# Logic_138.net
KiCad netlist of a schematic drawn in Altium Designer
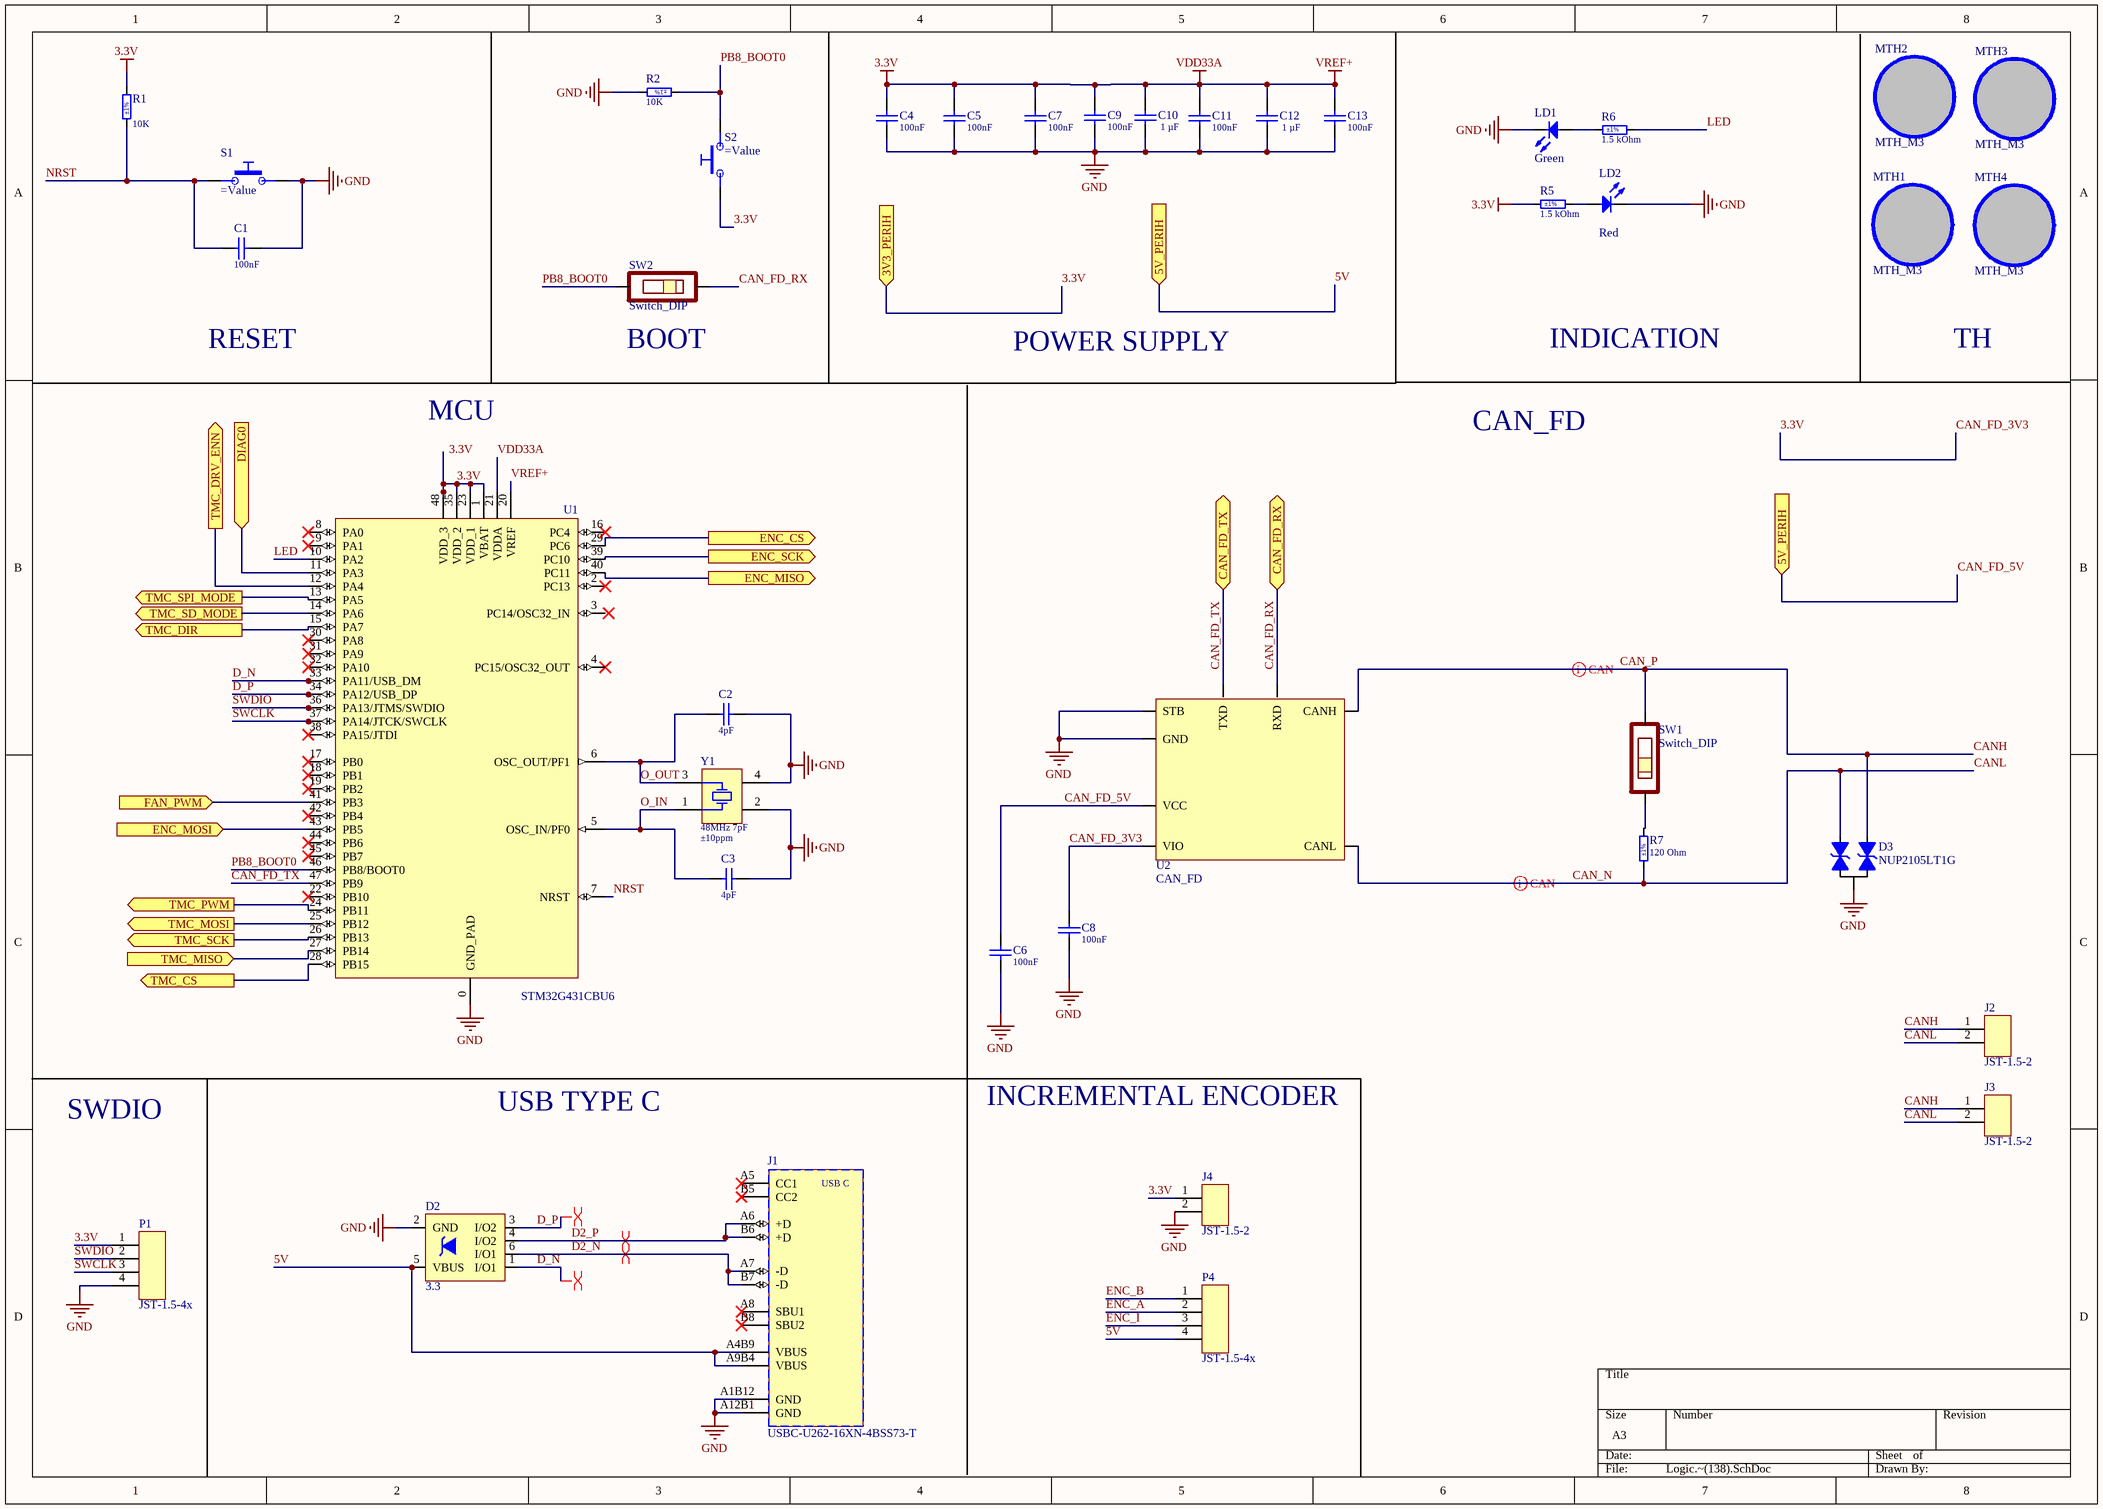
[diagram p0: Logic.~(138).SchDoc]

(export (version "E")
  (design (tool "Eeschema 10.0.6"))
  (components
    (comp (ref "C1")
      (value "100nF 16V X7R ±10%")
      (footprint "capasitors:0402")
      (description "Ceramic capacitor")
      (fields
        (field (name "VOLTAGE") "16V")
        (field (name "TOLERANCE") "±10%")
        (field (name "CAPACITANCE") "100nF")
      )
      (libsource (lib "passive") (part "Capacitor ceramic"))
    )
    (comp (ref "C2")
      (value "4pF 50V C0G (NP0) ±0.25 pF")
      (footprint "0402")
      (description "Ceramic capacitor")
      (fields
        (field (name "VOLTAGE") "50V")
        (field (name "TOLERANCE") "±0.25 pF")
        (field (name "CAPACITANCE") "4pF")
      )
      (libsource (lib "Integrated_Library_Rassipuha_ZEN") (part "Capacitor ceramic"))
    )
    (comp (ref "C3")
      (value "4pF 50V C0G (NP0) ±0.25 pF")
      (footprint "0402")
      (description "Ceramic capacitor")
      (fields
        (field (name "VOLTAGE") "50V")
        (field (name "TOLERANCE") "±0.25 pF")
        (field (name "CAPACITANCE") "4pF")
      )
      (libsource (lib "Integrated_Library_Rassipuha_ZEN") (part "Capacitor ceramic"))
    )
    (comp (ref "C4")
      (value "100nF 16V X7R ±10%")
      (footprint "capasitors:0402")
      (description "Ceramic capacitor")
      (fields
        (field (name "VOLTAGE") "16V")
        (field (name "TOLERANCE") "±10%")
        (field (name "CAPACITANCE") "100nF")
      )
      (libsource (lib "passive") (part "Capacitor ceramic"))
    )
    (comp (ref "C5")
      (value "100nF 16V X7R ±10%")
      (footprint "capasitors:0402")
      (description "Ceramic capacitor")
      (fields
        (field (name "VOLTAGE") "16V")
        (field (name "TOLERANCE") "±10%")
        (field (name "CAPACITANCE") "100nF")
      )
      (libsource (lib "passive") (part "Capacitor ceramic"))
    )
    (comp (ref "C6")
      (value "100nF 16V X7R ±10%")
      (footprint "capasitors:0402")
      (description "Ceramic capacitor")
      (fields
        (field (name "VOLTAGE") "16V")
        (field (name "TOLERANCE") "±10%")
        (field (name "CAPACITANCE") "100nF")
      )
      (libsource (lib "passive") (part "Capacitor ceramic"))
    )
    (comp (ref "C7")
      (value "100nF 16V X7R ±10%")
      (footprint "capasitors:0402")
      (description "Ceramic capacitor")
      (fields
        (field (name "VOLTAGE") "16V")
        (field (name "TOLERANCE") "±10%")
        (field (name "CAPACITANCE") "100nF")
      )
      (libsource (lib "passive") (part "Capacitor ceramic"))
    )
    (comp (ref "C8")
      (value "100nF 16V X7R ±10%")
      (footprint "capasitors:0402")
      (description "Ceramic capacitor")
      (fields
        (field (name "VOLTAGE") "16V")
        (field (name "TOLERANCE") "±10%")
        (field (name "CAPACITANCE") "100nF")
      )
      (libsource (lib "passive") (part "Capacitor ceramic"))
    )
    (comp (ref "C9")
      (value "100nF 16V X7R ±10%")
      (footprint "capasitors:0402")
      (description "Ceramic capacitor")
      (fields
        (field (name "VOLTAGE") "16V")
        (field (name "TOLERANCE") "±10%")
        (field (name "CAPACITANCE") "100nF")
      )
      (libsource (lib "passive") (part "Capacitor ceramic"))
    )
    (comp (ref "C10")
      (value "1 µF 16V X5R ±10%")
      (footprint "capasitors:0402")
      (description "Ceramic capacitor")
      (fields
        (field (name "VOLTAGE") "16V")
        (field (name "TOLERANCE") "±10%")
        (field (name "CAPACITANCE") " 1 µF")
      )
      (libsource (lib "passive") (part "Capacitor ceramic"))
    )
    (comp (ref "C11")
      (value "100nF 16V X7R ±10%")
      (footprint "capasitors:0402")
      (description "Ceramic capacitor")
      (fields
        (field (name "VOLTAGE") "16V")
        (field (name "TOLERANCE") "±10%")
        (field (name "CAPACITANCE") "100nF")
      )
      (libsource (lib "passive") (part "Capacitor ceramic"))
    )
    (comp (ref "C12")
      (value "1 µF 16V X5R ±10%")
      (footprint "capasitors:0402")
      (description "Ceramic capacitor")
      (fields
        (field (name "VOLTAGE") "16V")
        (field (name "TOLERANCE") "±10%")
        (field (name "CAPACITANCE") " 1 µF")
      )
      (libsource (lib "passive") (part "Capacitor ceramic"))
    )
    (comp (ref "C13")
      (value "100nF 16V X7R ±10%")
      (footprint "capasitors:0402")
      (description "Ceramic capacitor")
      (fields
        (field (name "VOLTAGE") "16V")
        (field (name "TOLERANCE") "±10%")
        (field (name "CAPACITANCE") "100nF")
      )
      (libsource (lib "passive") (part "Capacitor ceramic"))
    )
    (comp (ref "D2")
      (value "3.3")
      (footprint "SOT23-6L")
      (description "TWS")
      (fields (field (name "MANUFACTURER") "ST"))
      (libsource (lib "diodes") (part "TWS_USB_sot23"))
    )
    (comp (ref "D3")
      (value "VRWM=24V, VBR(Min)=26.2 V, VC=44 V")
      (footprint "SOT_SC:SOT-23")
      (description "Zener Diode double CC")
      (fields
        (field (name "NAME") "NUP2105LT1G")
        (field (name "MANUFACTURER") "ON")
        (field (name "HQ PART") "CP0103362")
      )
      (libsource (lib "diodes") (part "ZenerDiodeDoubleCCBidir"))
    )
    (comp (ref "J1")
      (value "USBC-U262-16XN-4BSS73-T")
      (footprint "KH-TYPE-C-16P-T")
      (libsource (lib "Integrated_Library_Connector_ZEN") (part "USBC-U262-16XN-4BSS73-T"))
    )
    (comp (ref "J2")
      (value "JST-1.5-2")
      (footprint "JST- 2 X - 1.5")
      (libsource (lib "Integrated_Library_Connector_ZEN") (part "JST-1.5-2"))
    )
    (comp (ref "J3")
      (value "JST-1.5-2")
      (footprint "JST- 2 X - 1.5")
      (libsource (lib "Integrated_Library_Connector_ZEN") (part "JST-1.5-2"))
    )
    (comp (ref "J4")
      (value "JST-1.5-2")
      (footprint "JST- 2 X - 1.5")
      (libsource (lib "Integrated_Library_Connector_ZEN") (part "JST-1.5-2"))
    )
    (comp (ref "LD1")
      (value "SZYY0402G (Green) /")
      (footprint "0402 GREEN FLAT")
      (description "Green LED")
      (fields (field (name "COLOR") "Green") (field (name "MANUFACTURER") "YONGYU"))
      (libsource (lib "Integrated_Library_Rassipuha_ZEN") (part "LED Green"))
    )
    (comp (ref "LD2")
      (value "SML-P11UTT86R (Red) /")
      (footprint "0402 RED FLAT")
      (description "Red LED")
      (fields (field (name "COLOR") "Red") (field (name "MANUFACTURER") "ROHM"))
      (libsource (lib "Integrated_Library_Rassipuha_ZEN") (part "LED Red"))
    )
    (comp (ref "MTH1")
      (value "MTH_M3")
      (footprint "MTH")
      (libsource (lib "Integrated_Library_CAN_MODULE") (part "MTH_M3"))
    )
    (comp (ref "MTH2")
      (value "MTH_M3")
      (footprint "MTH")
      (libsource (lib "Integrated_Library_CAN_MODULE") (part "MTH_M3"))
    )
    (comp (ref "MTH3")
      (value "MTH_M3")
      (footprint "MTH")
      (libsource (lib "Integrated_Library_CAN_MODULE") (part "MTH_M3"))
    )
    (comp (ref "MTH4")
      (value "MTH_M3")
      (footprint "MTH")
      (libsource (lib "Integrated_Library_CAN_MODULE") (part "MTH_M3"))
    )
    (comp (ref "P1")
      (value "JST-1.5-4x")
      (footprint "JST- 4X - 1.5")
      (libsource (lib "Integrated_Library_Connector_ZEN") (part "JST-1.5-4x"))
    )
    (comp (ref "P4")
      (value "JST-1.5-4x")
      (footprint "JST- 4X - 1.5")
      (libsource (lib "Integrated_Library_Connector_ZEN") (part "JST-1.5-4x"))
    )
    (comp (ref "R1")
      (value "10K 1/5W")
      (footprint "0402")
      (description "Thin Film Chip Resistor")
      (fields
        (field (name "POWER") "1/5W")
        (field (name "TOLERANCE") "±1%")
        (field (name "RESISTANCE") "10K")
      )
      (libsource (lib "Integrated_Library_Rassipuha_ZEN") (part "Resistor"))
    )
    (comp (ref "R2")
      (value "10K 1/5W")
      (footprint "0402")
      (description "Thin Film Chip Resistor")
      (fields
        (field (name "POWER") "1/5W")
        (field (name "TOLERANCE") "±1%")
        (field (name "RESISTANCE") "10K")
      )
      (libsource (lib "Integrated_Library_Rassipuha_ZEN") (part "Resistor"))
    )
    (comp (ref "R5")
      (value "1.5 kOhm 1/16W")
      (footprint "0402")
      (description "Thin Film Chip Resistor")
      (fields
        (field (name "POWER") "1/16W")
        (field (name "TOLERANCE") "±1%")
        (field (name "RESISTANCE") "1.5 kOhm")
      )
      (libsource (lib "Integrated_Library_Rassipuha_ZEN") (part "Resistor"))
    )
    (comp (ref "R6")
      (value "1.5 kOhm 1/16W")
      (footprint "0402")
      (description "Thin Film Chip Resistor")
      (fields
        (field (name "POWER") "1/16W")
        (field (name "TOLERANCE") "±1%")
        (field (name "RESISTANCE") "1.5 kOhm")
      )
      (libsource (lib "Integrated_Library_Rassipuha_ZEN") (part "Resistor"))
    )
    (comp (ref "R7")
      (value "120 Ohm 1/8 W")
      (footprint "resistor:0402")
      (description "Thick Film Chip Resistor")
      (fields
        (field (name "POWER") "1/8 W")
        (field (name "TOLERANCE") "±1%")
        (field (name "RESISTANCE") "120 Ohm")
      )
      (libsource (lib "passive") (part "Resistor"))
    )
    (comp (ref "S1")
      (value "~")
      (footprint "B3U3000P")
      (description "SMD Tactile switch")
      (libsource (lib "Integrated_Library_ElectroMechanical_Zen") (part "TactileButton2pin"))
    )
    (comp (ref "S2")
      (value "~")
      (footprint "B3U3000P")
      (description "SMD Tactile switch")
      (libsource (lib "") (part "TactileButton2pin_1"))
    )
    (comp (ref "SW1")
      (value "Switch_DIP")
      (footprint "SMD 2.9x5.4mm")
      (libsource (lib "Boards_for_CAN_MODULE") (part "Switch_DIP"))
    )
    (comp (ref "SW2")
      (value "Switch_DIP")
      (footprint "SMD 2.9x5.4mm")
      (libsource (lib "") (part "Switch_DIP_1"))
    )
    (comp (ref "U1")
      (value "STM32G431CBU6")
      (footprint "QFN-48-0.5-7x7_TP")
      (libsource (lib "Integrated_Library_IC_ZEN") (part "STM32G431CBU6"))
    )
    (comp (ref "U2")
      (value "CAN_FD")
      (footprint "SOIC-8")
      (libsource (lib "Boards_for_CAN_MODULE") (part "CAN_FD"))
    )
    (comp (ref "Y1")
      (value "48MHz 7pF ±10ppm")
      (footprint "2016")
      (description "Quartz crystal")
      (fields
        (field (name "FREQUENCY") "48MHz 7pF")
        (field (name "TOLERANCE") "±10ppm")
        (field (name "MANUFACTURER") "HD FREQUENCY")
      )
      (libsource (lib "Integrated_Library_IC_ZEN") (part "Crystal 4 pin"))
    )
  )
  (nets
    (net (code "1") (name "/5V") (class "Default")
      (node (ref "C6") (pin "2") (pinfunction "2_2") (pintype "passive"))
      (node (ref "D2") (pin "5") (pinfunction "VBUS_5") (pintype "passive"))
      (node (ref "J1") (pin "A4B9") (pinfunction "VBUS_A4B9") (pintype "power_in"))
      (node (ref "J1") (pin "A9B4") (pinfunction "VBUS_A9B4") (pintype "power_in"))
      (node (ref "P4") (pin "4") (pinfunction "4_4") (pintype "passive"))
      (node (ref "U2") (pin "3") (pinfunction "VCC_3") (pintype "passive"))
    )
    (net (code "2") (name "/CANH") (class "Default")
      (node (ref "D3") (pin "1") (pinfunction "1_1") (pintype "passive"))
      (node (ref "J2") (pin "1") (pinfunction "1_1") (pintype "passive"))
      (node (ref "J3") (pin "1") (pinfunction "1_1") (pintype "passive"))
      (node (ref "SW1") (pin "1") (pinfunction "1_1") (pintype "passive"))
      (node (ref "U2") (pin "7") (pinfunction "CANH_7") (pintype "passive"))
    )
    (net (code "3") (name "/CANL") (class "Default")
      (node (ref "D3") (pin "2") (pinfunction "2_2") (pintype "passive"))
      (node (ref "J2") (pin "2") (pinfunction "2_2") (pintype "passive"))
      (node (ref "J3") (pin "2") (pinfunction "2_2") (pintype "passive"))
      (node (ref "R7") (pin "1") (pinfunction "1_1") (pintype "passive"))
      (node (ref "U2") (pin "6") (pinfunction "CANL_6") (pintype "passive"))
    )
    (net (code "4") (name "/CAN_FD_RX") (class "Default")
      (node (ref "SW2") (pin "2") (pinfunction "2_2") (pintype "passive"))
      (node (ref "U2") (pin "4") (pinfunction "RXD_4") (pintype "passive"))
    )
    (net (code "5") (name "/CAN_FD_TX") (class "Default")
      (node (ref "U1") (pin "47") (pinfunction "PB9_47") (pintype "bidirectional"))
      (node (ref "U2") (pin "1") (pinfunction "TXD_1") (pintype "passive"))
    )
    (net (code "6") (name "/D2_N") (class "Default")
      (node (ref "D2") (pin "6") (pinfunction "I/O1_6") (pintype "passive"))
      (node (ref "J1") (pin "A7") (pinfunction "-D_A7") (pintype "bidirectional"))
      (node (ref "J1") (pin "B7") (pinfunction "-D_B7") (pintype "bidirectional"))
    )
    (net (code "7") (name "/D2_P") (class "Default")
      (node (ref "D2") (pin "4") (pinfunction "I/O2_4") (pintype "passive"))
      (node (ref "J1") (pin "A6") (pinfunction "+D_A6") (pintype "bidirectional"))
      (node (ref "J1") (pin "B6") (pinfunction "+D_B6") (pintype "bidirectional"))
    )
    (net (code "8") (name "/DIAG0") (class "Default")
      (node (ref "U1") (pin "11") (pinfunction "PA3_11") (pintype "bidirectional"))
    )
    (net (code "9") (name "/D_N") (class "Default")
      (node (ref "D2") (pin "1") (pinfunction "I/O1_1") (pintype "passive"))
      (node (ref "U1") (pin "33") (pinfunction "PA11/USB_DM_33") (pintype "bidirectional"))
    )
    (net (code "10") (name "/D_P") (class "Default")
      (node (ref "D2") (pin "3") (pinfunction "I/O2_3") (pintype "passive"))
      (node (ref "U1") (pin "34") (pinfunction "PA12/USB_DP_34") (pintype "bidirectional"))
    )
    (net (code "11") (name "/ENC_A") (class "Default")
      (node (ref "P4") (pin "2") (pinfunction "2_2") (pintype "passive"))
    )
    (net (code "12") (name "/ENC_B") (class "Default")
      (node (ref "P4") (pin "1") (pinfunction "1_1") (pintype "passive"))
    )
    (net (code "13") (name "/ENC_CS") (class "Default")
      (node (ref "U1") (pin "29") (pinfunction "PC6_29") (pintype "bidirectional"))
    )
    (net (code "14") (name "/ENC_I") (class "Default")
      (node (ref "P4") (pin "3") (pinfunction "3_3") (pintype "passive"))
    )
    (net (code "15") (name "/ENC_MISO") (class "Default")
      (node (ref "U1") (pin "40") (pinfunction "PC11_40") (pintype "bidirectional"))
    )
    (net (code "16") (name "/ENC_MOSI") (class "Default")
      (node (ref "U1") (pin "43") (pinfunction "PB5_43") (pintype "bidirectional"))
    )
    (net (code "17") (name "/ENC_SCK") (class "Default")
      (node (ref "U1") (pin "39") (pinfunction "PC10_39") (pintype "bidirectional"))
    )
    (net (code "18") (name "/FAN_PWM") (class "Default")
      (node (ref "U1") (pin "41") (pinfunction "PB3_41") (pintype "bidirectional"))
    )
    (net (code "19") (name "/LED") (class "Default")
      (node (ref "R6") (pin "2") (pinfunction "2_2") (pintype "passive"))
      (node (ref "U1") (pin "10") (pinfunction "PA2_10") (pintype "bidirectional"))
    )
    (net (code "20") (name "/NRST") (class "Default")
      (node (ref "C1") (pin "2") (pinfunction "2_2") (pintype "passive"))
      (node (ref "R1") (pin "1") (pinfunction "1_1") (pintype "passive"))
      (node (ref "S1") (pin "1") (pinfunction "1_1") (pintype "passive"))
      (node (ref "U1") (pin "7") (pinfunction "NRST_7") (pintype "bidirectional"))
    )
    (net (code "21") (name "/O_IN") (class "Default")
      (node (ref "C3") (pin "1") (pinfunction "1_1") (pintype "passive"))
      (node (ref "U1") (pin "5") (pinfunction "OSC_IN/PF0_5") (pintype "input"))
      (node (ref "Y1") (pin "1") (pinfunction "X_1") (pintype "passive"))
    )
    (net (code "22") (name "/O_OUT") (class "Default")
      (node (ref "C2") (pin "1") (pinfunction "1_1") (pintype "passive"))
      (node (ref "U1") (pin "6") (pinfunction "OSC_OUT/PF1_6") (pintype "output"))
      (node (ref "Y1") (pin "3") (pinfunction "X_3") (pintype "passive"))
    )
    (net (code "23") (name "/PB8_BOOT0") (class "Default")
      (node (ref "R2") (pin "1") (pinfunction "1_1") (pintype "passive"))
      (node (ref "S2") (pin "2") (pinfunction "2_2") (pintype "passive"))
      (node (ref "SW2") (pin "1") (pinfunction "1_1") (pintype "passive"))
      (node (ref "U1") (pin "46") (pinfunction "PB8/BOOT0_46") (pintype "bidirectional"))
    )
    (net (code "24") (name "/SWCLK") (class "Default")
      (node (ref "P1") (pin "3") (pinfunction "3_3") (pintype "passive"))
      (node (ref "U1") (pin "37") (pinfunction "PA14/JTCK/SWCLK_37") (pintype "bidirectional"))
    )
    (net (code "25") (name "/SWDIO") (class "Default")
      (node (ref "P1") (pin "2") (pinfunction "2_2") (pintype "passive"))
      (node (ref "U1") (pin "36") (pinfunction "PA13/JTMS/SWDIO_36") (pintype "bidirectional"))
    )
    (net (code "26") (name "/TMC_CS") (class "Default")
      (node (ref "U1") (pin "28") (pinfunction "PB15_28") (pintype "bidirectional"))
    )
    (net (code "27") (name "/TMC_DIR") (class "Default")
      (node (ref "U1") (pin "15") (pinfunction "PA7_15") (pintype "bidirectional"))
    )
    (net (code "28") (name "/TMC_DRV_ENN") (class "Default")
      (node (ref "U1") (pin "12") (pinfunction "PA4_12") (pintype "bidirectional"))
    )
    (net (code "29") (name "/TMC_MISO") (class "Default")
      (node (ref "U1") (pin "27") (pinfunction "PB14_27") (pintype "bidirectional"))
    )
    (net (code "30") (name "/TMC_MOSI") (class "Default")
      (node (ref "U1") (pin "25") (pinfunction "PB12_25") (pintype "bidirectional"))
    )
    (net (code "31") (name "/TMC_PWM") (class "Default")
      (node (ref "U1") (pin "24") (pinfunction "PB11_24") (pintype "bidirectional"))
    )
    (net (code "32") (name "/TMC_SCK") (class "Default")
      (node (ref "U1") (pin "26") (pinfunction "PB13_26") (pintype "bidirectional"))
    )
    (net (code "33") (name "/TMC_SD_MODE") (class "Default")
      (node (ref "U1") (pin "14") (pinfunction "PA6_14") (pintype "bidirectional"))
    )
    (net (code "34") (name "/TMC_SPI_MODE") (class "Default")
      (node (ref "U1") (pin "13") (pinfunction "PA5_13") (pintype "bidirectional"))
    )
    (net (code "35") (name "3.3V") (class "Default")
      (node (ref "C10") (pin "1") (pinfunction "1_1") (pintype "passive"))
      (node (ref "C11") (pin "2") (pinfunction "2_2") (pintype "passive"))
      (node (ref "C12") (pin "1") (pinfunction "1_1") (pintype "passive"))
      (node (ref "C13") (pin "2") (pinfunction "2_2") (pintype "passive"))
      (node (ref "C4") (pin "2") (pinfunction "2_2") (pintype "passive"))
      (node (ref "C5") (pin "2") (pinfunction "2_2") (pintype "passive"))
      (node (ref "C7") (pin "2") (pinfunction "2_2") (pintype "passive"))
      (node (ref "C8") (pin "2") (pinfunction "2_2") (pintype "passive"))
      (node (ref "C9") (pin "2") (pinfunction "2_2") (pintype "passive"))
      (node (ref "J4") (pin "1") (pinfunction "1_1") (pintype "passive"))
      (node (ref "P1") (pin "1") (pinfunction "1_1") (pintype "passive"))
      (node (ref "R1") (pin "2") (pinfunction "2_2") (pintype "passive"))
      (node (ref "R5") (pin "1") (pinfunction "1_1") (pintype "passive"))
      (node (ref "S2") (pin "1") (pinfunction "1_1") (pintype "passive"))
      (node (ref "U1") (pin "1") (pinfunction "VBAT_1") (pintype "power_in"))
      (node (ref "U1") (pin "20") (pinfunction "VREF_20") (pintype "power_in"))
      (node (ref "U1") (pin "21") (pinfunction "VDDA_21") (pintype "power_in"))
      (node (ref "U1") (pin "23") (pinfunction "VDD_1_23") (pintype "power_in"))
      (node (ref "U1") (pin "35") (pinfunction "VDD_2_35") (pintype "power_in"))
      (node (ref "U1") (pin "48") (pinfunction "VDD_3_48") (pintype "power_in"))
      (node (ref "U2") (pin "5") (pinfunction "VIO_5") (pintype "passive"))
    )
    (net (code "36") (name "GND") (class "Default")
      (node (ref "C1") (pin "1") (pinfunction "1_1") (pintype "passive"))
      (node (ref "C10") (pin "2") (pinfunction "2_2") (pintype "passive"))
      (node (ref "C11") (pin "1") (pinfunction "1_1") (pintype "passive"))
      (node (ref "C12") (pin "2") (pinfunction "2_2") (pintype "passive"))
      (node (ref "C13") (pin "1") (pinfunction "1_1") (pintype "passive"))
      (node (ref "C2") (pin "2") (pinfunction "2_2") (pintype "passive"))
      (node (ref "C3") (pin "2") (pinfunction "2_2") (pintype "passive"))
      (node (ref "C4") (pin "1") (pinfunction "1_1") (pintype "passive"))
      (node (ref "C5") (pin "1") (pinfunction "1_1") (pintype "passive"))
      (node (ref "C6") (pin "1") (pinfunction "1_1") (pintype "passive"))
      (node (ref "C7") (pin "1") (pinfunction "1_1") (pintype "passive"))
      (node (ref "C8") (pin "1") (pinfunction "1_1") (pintype "passive"))
      (node (ref "C9") (pin "1") (pinfunction "1_1") (pintype "passive"))
      (node (ref "D2") (pin "2") (pinfunction "GND_2") (pintype "passive"))
      (node (ref "D3") (pin "3") (pinfunction "3_3") (pintype "passive"))
      (node (ref "J1") (pin "A12B1") (pinfunction "GND_A12B1") (pintype "power_in"))
      (node (ref "J1") (pin "A1B12") (pinfunction "GND_A1B12") (pintype "power_in"))
      (node (ref "J4") (pin "2") (pinfunction "2_2") (pintype "passive"))
      (node (ref "LD1") (pin "2") (pinfunction "C_2") (pintype "passive"))
      (node (ref "LD2") (pin "2") (pinfunction "C_2") (pintype "passive"))
      (node (ref "P1") (pin "4") (pinfunction "4_4") (pintype "passive"))
      (node (ref "R2") (pin "2") (pinfunction "2_2") (pintype "passive"))
      (node (ref "S1") (pin "2") (pinfunction "2_2") (pintype "passive"))
      (node (ref "U1") (pin "0") (pinfunction "GND_PAD_0") (pintype "power_in"))
      (node (ref "U2") (pin "2") (pinfunction "GND_2") (pintype "passive"))
      (node (ref "U2") (pin "8") (pinfunction "STB_8") (pintype "passive"))
      (node (ref "Y1") (pin "2") (pinfunction "GND_2") (pintype "power_in"))
      (node (ref "Y1") (pin "4") (pinfunction "GND_4") (pintype "power_in"))
    )
    (net (code "37") (name "Net-(LD1-A)") (class "Default")
      (node (ref "LD1") (pin "1") (pinfunction "A_1") (pintype "passive"))
      (node (ref "R6") (pin "1") (pinfunction "1_1") (pintype "passive"))
    )
    (net (code "38") (name "Net-(LD2-A)") (class "Default")
      (node (ref "LD2") (pin "1") (pinfunction "A_1") (pintype "passive"))
      (node (ref "R5") (pin "2") (pinfunction "2_2") (pintype "passive"))
    )
    (net (code "39") (name "Net-(R7-Pad2)") (class "Default")
      (node (ref "R7") (pin "2") (pinfunction "2_2") (pintype "passive"))
      (node (ref "SW1") (pin "2") (pinfunction "2_2") (pintype "passive"))
    )
    (net (code "40") (name "unconnected-(J1-CC1-PadA5)") (class "Default")
      (node (ref "J1") (pin "A5") (pinfunction "CC1_A5") (pintype "passive+no_connect"))
    )
    (net (code "41") (name "unconnected-(J1-CC2-PadB5)") (class "Default")
      (node (ref "J1") (pin "B5") (pinfunction "CC2_B5") (pintype "passive+no_connect"))
    )
    (net (code "42") (name "unconnected-(J1-SBU1-PadA8)") (class "Default")
      (node (ref "J1") (pin "A8") (pinfunction "SBU1_A8") (pintype "passive+no_connect"))
    )
    (net (code "43") (name "unconnected-(J1-SBU2-PadB8)") (class "Default")
      (node (ref "J1") (pin "B8") (pinfunction "SBU2_B8") (pintype "passive+no_connect"))
    )
    (net (code "44") (name "unconnected-(U1-PA0-Pad8)") (class "Default")
      (node (ref "U1") (pin "8") (pinfunction "PA0_8") (pintype "bidirectional+no_connect"))
    )
    (net (code "45") (name "unconnected-(U1-PA1-Pad9)") (class "Default")
      (node (ref "U1") (pin "9") (pinfunction "PA1_9") (pintype "bidirectional+no_connect"))
    )
    (net (code "46") (name "unconnected-(U1-PA8-Pad30)") (class "Default")
      (node (ref "U1") (pin "30") (pinfunction "PA8_30") (pintype "bidirectional+no_connect"))
    )
    (net (code "47") (name "unconnected-(U1-PA9-Pad31)") (class "Default")
      (node (ref "U1") (pin "31") (pinfunction "PA9_31") (pintype "bidirectional+no_connect"))
    )
    (net (code "48") (name "unconnected-(U1-PA10-Pad32)") (class "Default")
      (node (ref "U1") (pin "32") (pinfunction "PA10_32") (pintype "bidirectional+no_connect"))
    )
    (net (code "49") (name "unconnected-(U1-PA15{slash}JTDI-Pad38)") (class "Default")
      (node (ref "U1") (pin "38") (pinfunction "PA15/JTDI_38") (pintype "bidirectional+no_connect"))
    )
    (net (code "50") (name "unconnected-(U1-PB0-Pad17)") (class "Default")
      (node (ref "U1") (pin "17") (pinfunction "PB0_17") (pintype "bidirectional+no_connect"))
    )
    (net (code "51") (name "unconnected-(U1-PB1-Pad18)") (class "Default")
      (node (ref "U1") (pin "18") (pinfunction "PB1_18") (pintype "bidirectional+no_connect"))
    )
    (net (code "52") (name "unconnected-(U1-PB2-Pad19)") (class "Default")
      (node (ref "U1") (pin "19") (pinfunction "PB2_19") (pintype "bidirectional+no_connect"))
    )
    (net (code "53") (name "unconnected-(U1-PB4-Pad42)") (class "Default")
      (node (ref "U1") (pin "42") (pinfunction "PB4_42") (pintype "bidirectional+no_connect"))
    )
    (net (code "54") (name "unconnected-(U1-PB6-Pad44)") (class "Default")
      (node (ref "U1") (pin "44") (pinfunction "PB6_44") (pintype "bidirectional+no_connect"))
    )
    (net (code "55") (name "unconnected-(U1-PB7-Pad45)") (class "Default")
      (node (ref "U1") (pin "45") (pinfunction "PB7_45") (pintype "bidirectional+no_connect"))
    )
    (net (code "56") (name "unconnected-(U1-PB10-Pad22)") (class "Default")
      (node (ref "U1") (pin "22") (pinfunction "PB10_22") (pintype "bidirectional+no_connect"))
    )
    (net (code "57") (name "unconnected-(U1-PC4-Pad16)") (class "Default")
      (node (ref "U1") (pin "16") (pinfunction "PC4_16") (pintype "bidirectional+no_connect"))
    )
    (net (code "58") (name "unconnected-(U1-PC13-Pad2)") (class "Default")
      (node (ref "U1") (pin "2") (pinfunction "PC13_2") (pintype "bidirectional+no_connect"))
    )
    (net (code "59") (name "unconnected-(U1-PC14{slash}OSC32_IN-Pad3)") (class "Default")
      (node (ref "U1") (pin "3") (pinfunction "PC14/OSC32_IN_3") (pintype "bidirectional"))
    )
    (net (code "60") (name "unconnected-(U1-PC15{slash}OSC32_OUT-Pad4)") (class "Default")
      (node (ref "U1") (pin "4") (pinfunction "PC15/OSC32_OUT_4") (pintype "bidirectional+no_connect"))
    )
  )
)
